# Servo_Trigger.net
KiCad netlist of a schematic drawn in EAGLE
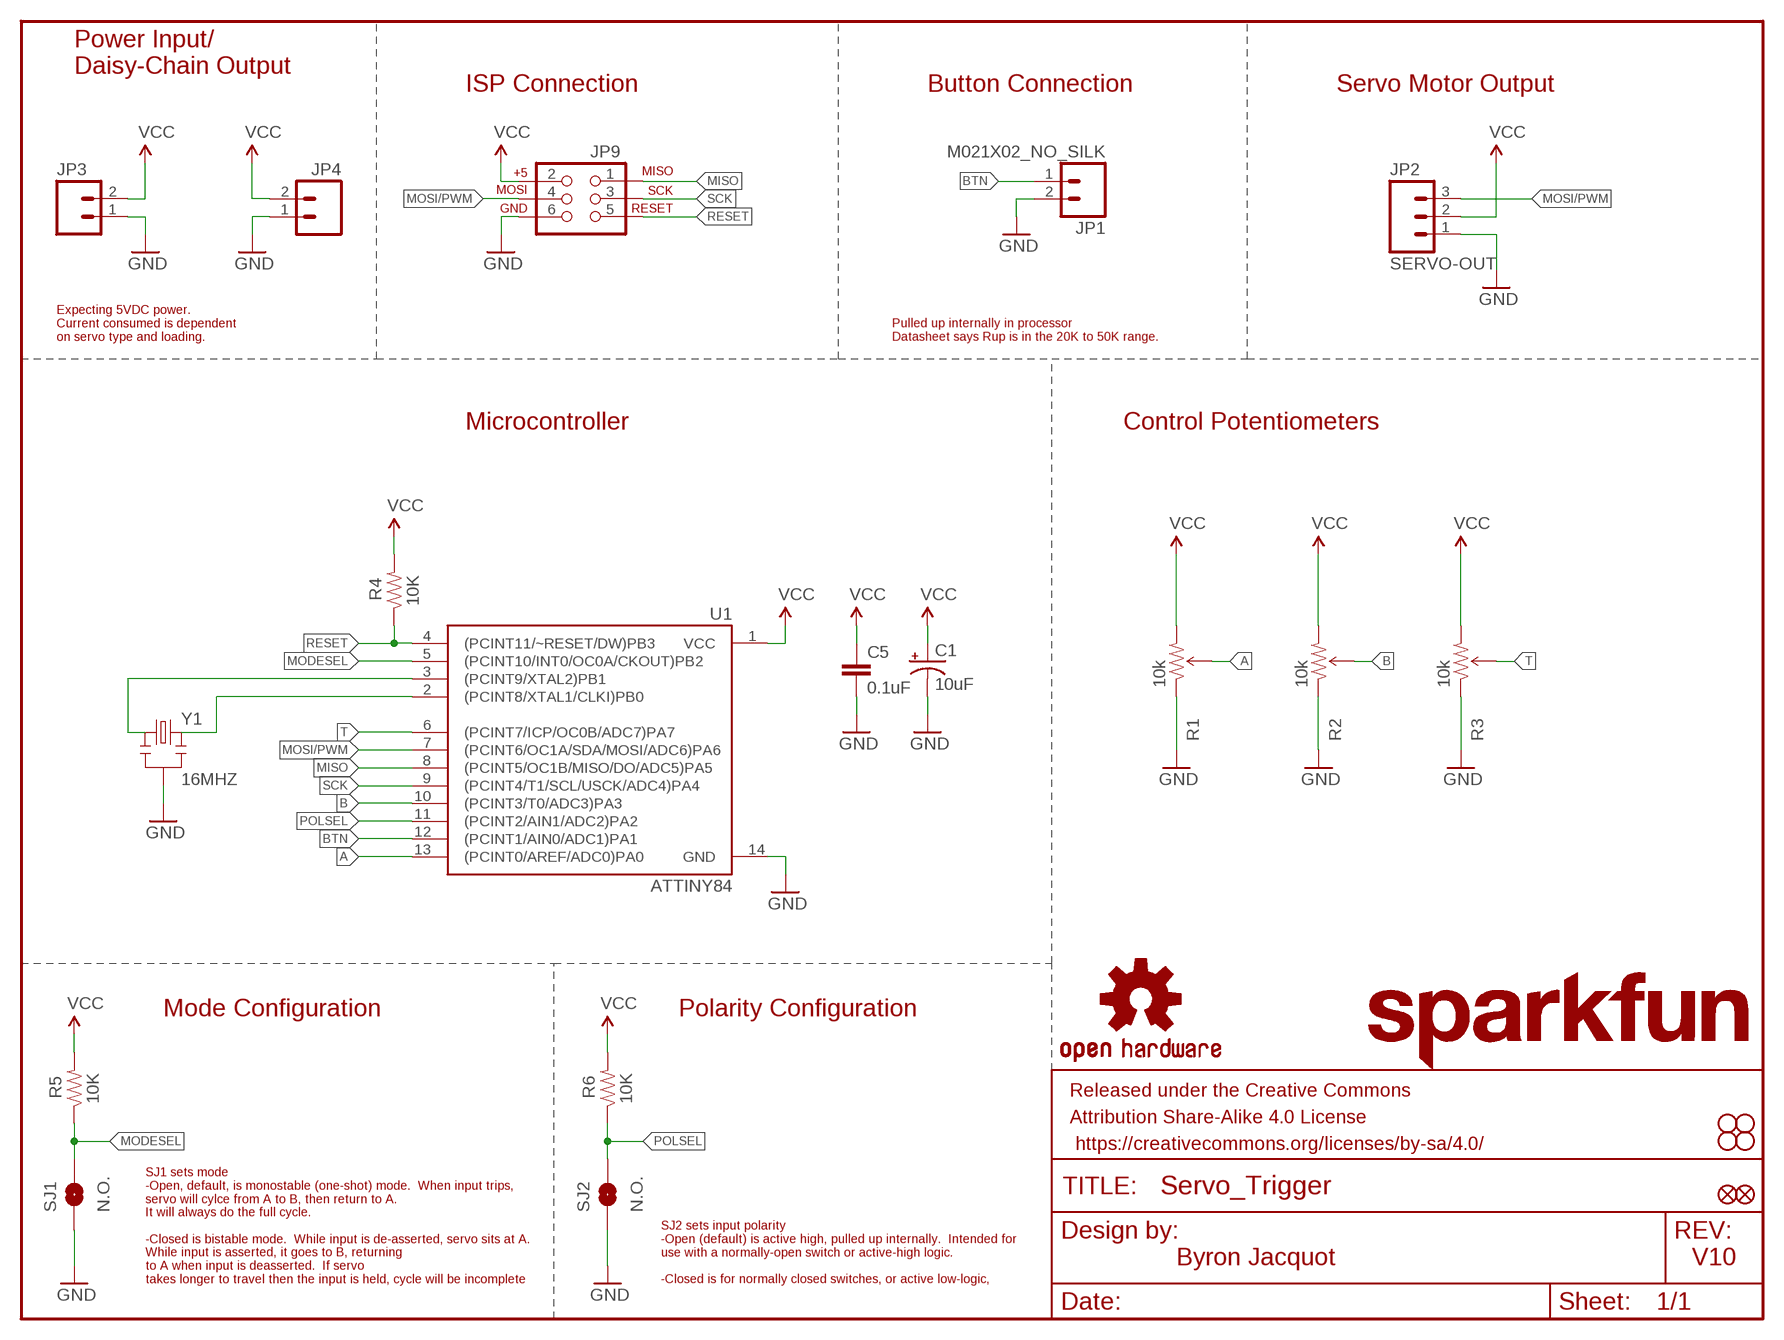
[diagram p0: schematic, sheet 1]

(export (version "E")
  (design (tool "Eeschema 10.0.6"))
  (components
    (comp (ref "C1")
      (value "10uF")
      (footprint "eagle-import:EIA3216")
      (libsource (lib "eagle-import") (part "10UF-16V-10%(TANT)"))
    )
    (comp (ref "C5")
      (value "0.1uF")
      (footprint "eagle-import:0603-CAP")
      (libsource (lib "eagle-import") (part "0.1UF-25V(+80/-20%)(0603)"))
    )
    (comp (ref "FID1")
      (value "FIDUCIALUFIDUCIAL")
      (footprint "eagle-import:MICRO-FIDUCIAL")
      (libsource (lib "eagle-import") (part "FIDUCIALUFIDUCIAL"))
    )
    (comp (ref "FID2")
      (value "FIDUCIALUFIDUCIAL")
      (footprint "eagle-import:MICRO-FIDUCIAL")
      (libsource (lib "eagle-import") (part "FIDUCIALUFIDUCIAL"))
    )
    (comp (ref "FRAME1")
      (value "FRAME-LETTER")
      (footprint "eagle-import:CREATIVE_COMMONS")
      (libsource (lib "eagle-import") (part "FRAME-LETTER"))
    )
    (comp (ref "JP1")
      (value "M021X02_NO_SILK")
      (footprint "eagle-import:1X02_NO_SILK")
      (libsource (lib "eagle-import") (part "M021X02_NO_SILK"))
    )
    (comp (ref "JP2")
      (value "SERVO-OUT")
      (footprint "eagle-import:1X03_NO_SILK")
      (libsource (lib "eagle-import") (part "M031X03_NO_SILK"))
    )
    (comp (ref "JP3")
      (value "M021X02_NO_SILK")
      (footprint "eagle-import:1X02_NO_SILK")
      (libsource (lib "eagle-import") (part "M021X02_NO_SILK"))
    )
    (comp (ref "JP4")
      (value "M021X02_NO_SILK")
      (footprint "eagle-import:1X02_NO_SILK")
      (libsource (lib "eagle-import") (part "M021X02_NO_SILK"))
    )
    (comp (ref "JP9")
      (value "AVR_SPI_PRG_6PTH")
      (footprint "eagle-import:2X3")
      (libsource (lib "eagle-import") (part "AVR_SPI_PRG_6PTH"))
    )
    (comp (ref "LOGO1")
      (value "OSHW-LOGOM")
      (footprint "eagle-import:OSHW-LOGO-M")
      (libsource (lib "eagle-import") (part "OSHW-LOGOM"))
    )
    (comp (ref "LOGO2")
      (value "SFE_LOGO_NAME.2_INCH")
      (footprint "eagle-import:SFE_LOGO_NAME_.2")
      (libsource (lib "eagle-import") (part "SFE_LOGO_NAME.2_INCH"))
    )
    (comp (ref "R1")
      (value "10k")
      (footprint "eagle-import:TRIMPOT_5MM")
      (libsource (lib "eagle-import") (part "TRIMPOTRES-11156"))
    )
    (comp (ref "R2")
      (value "10k")
      (footprint "eagle-import:TRIMPOT_5MM")
      (libsource (lib "eagle-import") (part "TRIMPOTRES-11156"))
    )
    (comp (ref "R3")
      (value "10k")
      (footprint "eagle-import:TRIMPOT_5MM")
      (libsource (lib "eagle-import") (part "TRIMPOTRES-11156"))
    )
    (comp (ref "R4")
      (value "10K")
      (footprint "eagle-import:0603-RES")
      (libsource (lib "eagle-import") (part "10KOHM-1/10W-1%(0603)0603"))
    )
    (comp (ref "R5")
      (value "10K")
      (footprint "eagle-import:0603-RES")
      (libsource (lib "eagle-import") (part "10KOHM-1/10W-1%(0603)0603"))
    )
    (comp (ref "R6")
      (value "10K")
      (footprint "eagle-import:0603-RES")
      (libsource (lib "eagle-import") (part "10KOHM-1/10W-1%(0603)0603"))
    )
    (comp (ref "SJ1")
      (value "N.O.")
      (footprint "eagle-import:PAD-JUMPER-2-NO_YES_SILK")
      (libsource (lib "eagle-import") (part "JUMPER-PAD-2-NOYES_SILK"))
    )
    (comp (ref "SJ2")
      (value "N.O.")
      (footprint "eagle-import:PAD-JUMPER-2-NO_YES_SILK")
      (libsource (lib "eagle-import") (part "JUMPER-PAD-2-NOYES_SILK"))
    )
    (comp (ref "STANDOFF1")
      (value "STAND-OFF")
      (footprint "eagle-import:STAND-OFF")
      (libsource (lib "eagle-import") (part "STAND-OFF"))
    )
    (comp (ref "STANDOFF2")
      (value "STAND-OFF")
      (footprint "eagle-import:STAND-OFF")
      (libsource (lib "eagle-import") (part "STAND-OFF"))
    )
    (comp (ref "STANDOFF3")
      (value "STAND-OFF")
      (footprint "eagle-import:STAND-OFF")
      (libsource (lib "eagle-import") (part "STAND-OFF"))
    )
    (comp (ref "STANDOFF4")
      (value "STAND-OFF")
      (footprint "eagle-import:STAND-OFF")
      (libsource (lib "eagle-import") (part "STAND-OFF"))
    )
    (comp (ref "U1")
      (value "ATTINY84")
      (footprint "eagle-import:SO14")
      (libsource (lib "eagle-import") (part "ATTINY84"))
    )
    (comp (ref "Y1")
      (value "16MHZ")
      (footprint "eagle-import:RESONATOR-SMD")
      (libsource (lib "eagle-import") (part "RESONATOR16MHZ"))
    )
  )
  (nets
    (net (code "1") (name "A") (class "Default")
      (node (ref "R1") (pin "B") (pinfunction "WIPER_B") (pintype "passive"))
      (node (ref "U1") (pin "13") (pinfunction "(PCINT0/AREF/ADC0)PA0_13") (pintype "bidirectional"))
    )
    (net (code "2") (name "B") (class "Default")
      (node (ref "R2") (pin "B") (pinfunction "WIPER_B") (pintype "passive"))
      (node (ref "U1") (pin "10") (pinfunction "(PCINT3/T0/ADC3)PA3_10") (pintype "bidirectional"))
    )
    (net (code "3") (name "BTN") (class "Default")
      (node (ref "JP1") (pin "1") (pinfunction "1_1") (pintype "passive"))
      (node (ref "U1") (pin "12") (pinfunction "(PCINT1/AIN0/ADC1)PA1_12") (pintype "bidirectional"))
    )
    (net (code "4") (name "GND") (class "Default")
      (node (ref "C1") (pin "C") (pinfunction "-_C") (pintype "passive"))
      (node (ref "C5") (pin "2") (pinfunction "2_2") (pintype "passive"))
      (node (ref "JP1") (pin "2") (pinfunction "2_2") (pintype "passive"))
      (node (ref "JP2") (pin "1") (pinfunction "1_1") (pintype "passive"))
      (node (ref "JP3") (pin "1") (pinfunction "1_1") (pintype "passive"))
      (node (ref "JP4") (pin "1") (pinfunction "1_1") (pintype "passive"))
      (node (ref "JP9") (pin "6") (pinfunction "6_6") (pintype "passive"))
      (node (ref "R1") (pin "A") (pinfunction "CCW_A") (pintype "passive"))
      (node (ref "R2") (pin "A") (pinfunction "CCW_A") (pintype "passive"))
      (node (ref "R3") (pin "A") (pinfunction "CCW_A") (pintype "passive"))
      (node (ref "SJ1") (pin "1") (pinfunction "1_1") (pintype "passive"))
      (node (ref "SJ2") (pin "1") (pinfunction "1_1") (pintype "passive"))
      (node (ref "U1") (pin "14") (pinfunction "GND_14") (pintype "bidirectional"))
      (node (ref "Y1") (pin "2") (pinfunction "2_2") (pintype "passive"))
    )
    (net (code "5") (name "MISO") (class "Default")
      (node (ref "JP9") (pin "1") (pinfunction "1_1") (pintype "passive"))
      (node (ref "U1") (pin "8") (pinfunction "(PCINT5/OC1B/MISO/DO/ADC5)PA5_8") (pintype "bidirectional"))
    )
    (net (code "6") (name "MODESEL") (class "Default")
      (node (ref "R5") (pin "1") (pinfunction "1_1") (pintype "passive"))
      (node (ref "SJ1") (pin "2") (pinfunction "2_2") (pintype "passive"))
      (node (ref "U1") (pin "5") (pinfunction "(PCINT10/INT0/OC0A/CKOUT)PB2_5") (pintype "bidirectional"))
    )
    (net (code "7") (name "MOSI{slash}PWM") (class "Default")
      (node (ref "JP2") (pin "3") (pinfunction "3_3") (pintype "passive"))
      (node (ref "JP9") (pin "4") (pinfunction "4_4") (pintype "passive"))
      (node (ref "U1") (pin "7") (pinfunction "(PCINT6/OC1A/SDA/MOSI/ADC6)PA6_7") (pintype "bidirectional"))
    )
    (net (code "8") (name "Net-(U1-(PCINT8{slash}XTAL1{slash}CLKI)PB0)") (class "Default")
      (node (ref "U1") (pin "2") (pinfunction "(PCINT8/XTAL1/CLKI)PB0_2") (pintype "bidirectional"))
      (node (ref "Y1") (pin "3") (pinfunction "3_3") (pintype "passive"))
    )
    (net (code "9") (name "Net-(U1-(PCINT9{slash}XTAL2)PB1)") (class "Default")
      (node (ref "U1") (pin "3") (pinfunction "(PCINT9/XTAL2)PB1_3") (pintype "bidirectional"))
      (node (ref "Y1") (pin "1") (pinfunction "1_1") (pintype "passive"))
    )
    (net (code "10") (name "POLSEL") (class "Default")
      (node (ref "R6") (pin "1") (pinfunction "1_1") (pintype "passive"))
      (node (ref "SJ2") (pin "2") (pinfunction "2_2") (pintype "passive"))
      (node (ref "U1") (pin "11") (pinfunction "(PCINT2/AIN1/ADC2)PA2_11") (pintype "bidirectional"))
    )
    (net (code "11") (name "RESET") (class "Default")
      (node (ref "JP9") (pin "5") (pinfunction "5_5") (pintype "passive"))
      (node (ref "R4") (pin "1") (pinfunction "1_1") (pintype "passive"))
      (node (ref "U1") (pin "4") (pinfunction "(PCINT11/~{RESET/DW})PB3_4") (pintype "bidirectional"))
    )
    (net (code "12") (name "SCK") (class "Default")
      (node (ref "JP9") (pin "3") (pinfunction "3_3") (pintype "passive"))
      (node (ref "U1") (pin "9") (pinfunction "(PCINT4/T1/SCL/USCK/ADC4)PA4_9") (pintype "bidirectional"))
    )
    (net (code "13") (name "T") (class "Default")
      (node (ref "R3") (pin "B") (pinfunction "WIPER_B") (pintype "passive"))
      (node (ref "U1") (pin "6") (pinfunction "(PCINT7/ICP/OC0B/ADC7)PA7_6") (pintype "bidirectional"))
    )
    (net (code "14") (name "VCC") (class "Default")
      (node (ref "C1") (pin "A") (pinfunction "+_A") (pintype "passive"))
      (node (ref "C5") (pin "1") (pinfunction "1_1") (pintype "passive"))
      (node (ref "JP2") (pin "2") (pinfunction "2_2") (pintype "passive"))
      (node (ref "JP3") (pin "2") (pinfunction "2_2") (pintype "passive"))
      (node (ref "JP4") (pin "2") (pinfunction "2_2") (pintype "passive"))
      (node (ref "JP9") (pin "2") (pinfunction "2_2") (pintype "passive"))
      (node (ref "R1") (pin "C") (pinfunction "CW_C") (pintype "passive"))
      (node (ref "R2") (pin "C") (pinfunction "CW_C") (pintype "passive"))
      (node (ref "R3") (pin "C") (pinfunction "CW_C") (pintype "passive"))
      (node (ref "R4") (pin "2") (pinfunction "2_2") (pintype "passive"))
      (node (ref "R5") (pin "2") (pinfunction "2_2") (pintype "passive"))
      (node (ref "R6") (pin "2") (pinfunction "2_2") (pintype "passive"))
      (node (ref "U1") (pin "1") (pinfunction "VCC_1") (pintype "bidirectional"))
    )
  )
)
